# SinglePowerSupply.net
KiCad netlist of a schematic drawn in EAGLE
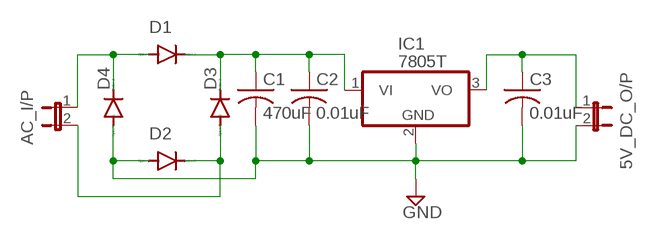
[diagram p0: schematic, sheet 1]

(export (version "E")
  (design (tool "Eeschema 10.0.6"))
  (components
    (comp (ref "5V_DC_O/P")
      (value "JP1E")
      (footprint "eagle-import:JP1")
      (libsource (lib "eagle-import") (part "JP1E"))
    )
    (comp (ref "AC_I/P")
      (value "JP1E")
      (footprint "eagle-import:JP1")
      (libsource (lib "eagle-import") (part "JP1E"))
    )
    (comp (ref "C1")
      (value "470uF")
      (footprint "eagle-import:C025_050-025X075")
      (libsource (lib "eagle-import") (part "C-US025_050-025X075"))
    )
    (comp (ref "C2")
      (value "0.01uF")
      (footprint "eagle-import:C025_050-025X075")
      (libsource (lib "eagle-import") (part "C-US025_050-025X075"))
    )
    (comp (ref "C3")
      (value "0.01uF")
      (footprint "eagle-import:C025_050-025X075")
      (libsource (lib "eagle-import") (part "C-US025_050-025X075"))
    )
    (comp (ref "D1")
      (value "1N4004")
      (footprint "eagle-import:DO41-10")
      (libsource (lib "eagle-import") (part "1N4004"))
    )
    (comp (ref "D2")
      (value "1N4004")
      (footprint "eagle-import:DO41-10")
      (libsource (lib "eagle-import") (part "1N4004"))
    )
    (comp (ref "D3")
      (value "1N4004")
      (footprint "eagle-import:DO41-10")
      (libsource (lib "eagle-import") (part "1N4004"))
    )
    (comp (ref "D4")
      (value "1N4004")
      (footprint "eagle-import:DO41-10")
      (libsource (lib "eagle-import") (part "1N4004"))
    )
    (comp (ref "IC1")
      (value "7805T")
      (footprint "eagle-import:TO220H")
      (libsource (lib "eagle-import") (part "78T05"))
    )
  )
  (nets
    (net (code "1") (name "GND") (class "Default")
      (node (ref "5V_DC_O/P") (pin "2") (pinfunction "2_2") (pintype "passive"))
      (node (ref "C1") (pin "2") (pinfunction "2_2") (pintype "passive"))
      (node (ref "C2") (pin "2") (pinfunction "2_2") (pintype "passive"))
      (node (ref "C3") (pin "2") (pinfunction "2_2") (pintype "passive"))
      (node (ref "D2") (pin "A") (pinfunction "A_A") (pintype "passive"))
      (node (ref "D4") (pin "A") (pinfunction "A_A") (pintype "passive"))
      (node (ref "IC1") (pin "2") (pinfunction "GND_2") (pintype "passive"))
    )
    (net (code "2") (name "Net-(AC_I/P-Pad1)") (class "Default")
      (node (ref "AC_I/P") (pin "1") (pinfunction "1_1") (pintype "passive"))
      (node (ref "D1") (pin "A") (pinfunction "A_A") (pintype "passive"))
      (node (ref "D4") (pin "C") (pinfunction "C_C") (pintype "passive"))
    )
    (net (code "3") (name "Net-(AC_I/P-Pad2)") (class "Default")
      (node (ref "AC_I/P") (pin "2") (pinfunction "2_2") (pintype "passive"))
      (node (ref "D2") (pin "C") (pinfunction "C_C") (pintype "passive"))
      (node (ref "D3") (pin "A") (pinfunction "A_A") (pintype "passive"))
    )
    (net (code "4") (name "Net-(IC1-VI)") (class "Default")
      (node (ref "C1") (pin "1") (pinfunction "1_1") (pintype "passive"))
      (node (ref "C2") (pin "1") (pinfunction "1_1") (pintype "passive"))
      (node (ref "D1") (pin "C") (pinfunction "C_C") (pintype "passive"))
      (node (ref "D3") (pin "C") (pinfunction "C_C") (pintype "passive"))
      (node (ref "IC1") (pin "1") (pinfunction "VI_1") (pintype "input"))
    )
    (net (code "5") (name "Net-(IC1-VO)") (class "Default")
      (node (ref "5V_DC_O/P") (pin "1") (pinfunction "1_1") (pintype "passive"))
      (node (ref "C3") (pin "1") (pinfunction "1_1") (pintype "passive"))
      (node (ref "IC1") (pin "3") (pinfunction "VO_3") (pintype "passive"))
    )
  )
)
